# K_line_ESP32.net
KiCad netlist of a schematic drawn in EAGLE
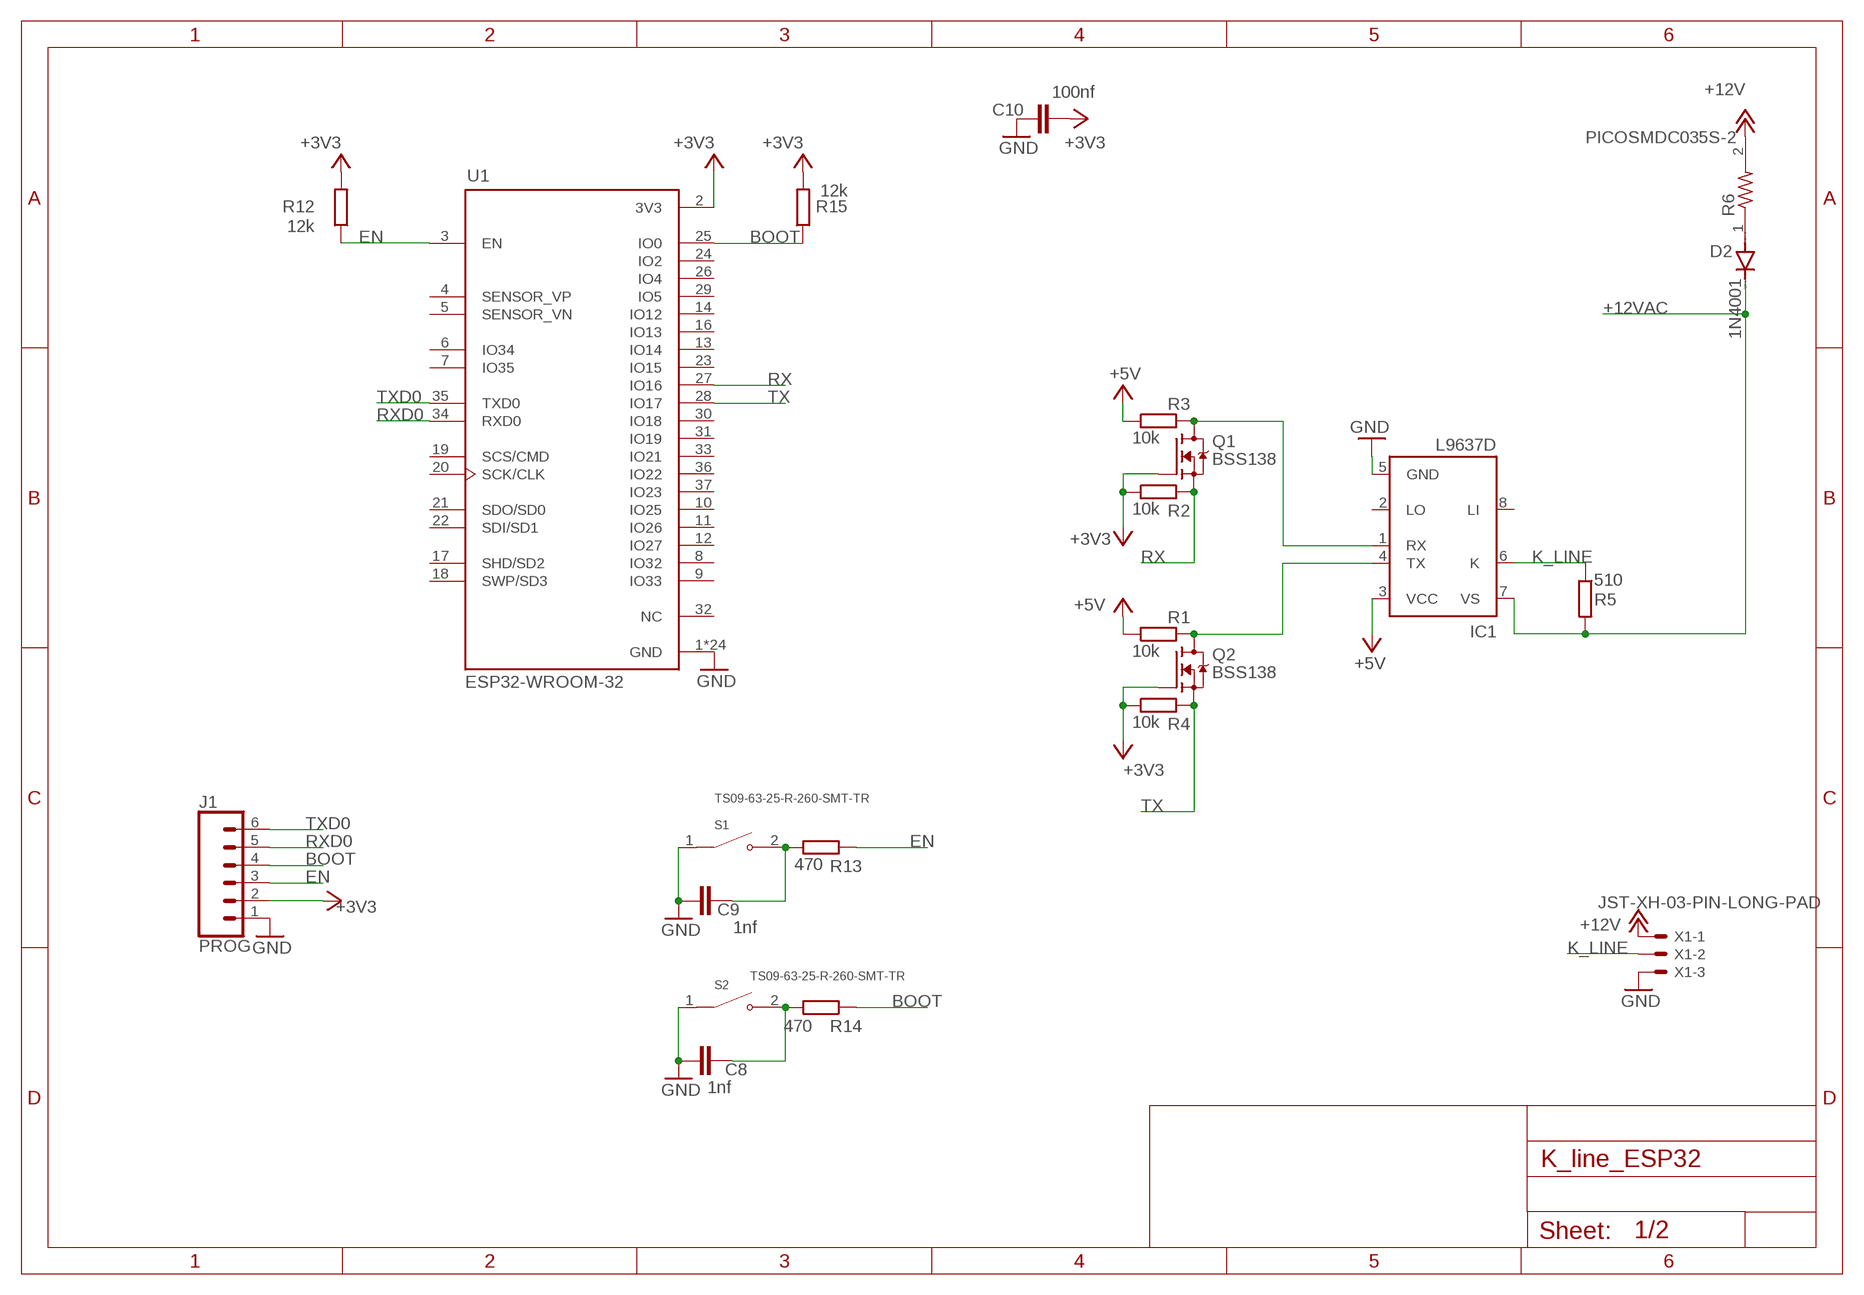
[diagram p0: schematic, sheet 1]
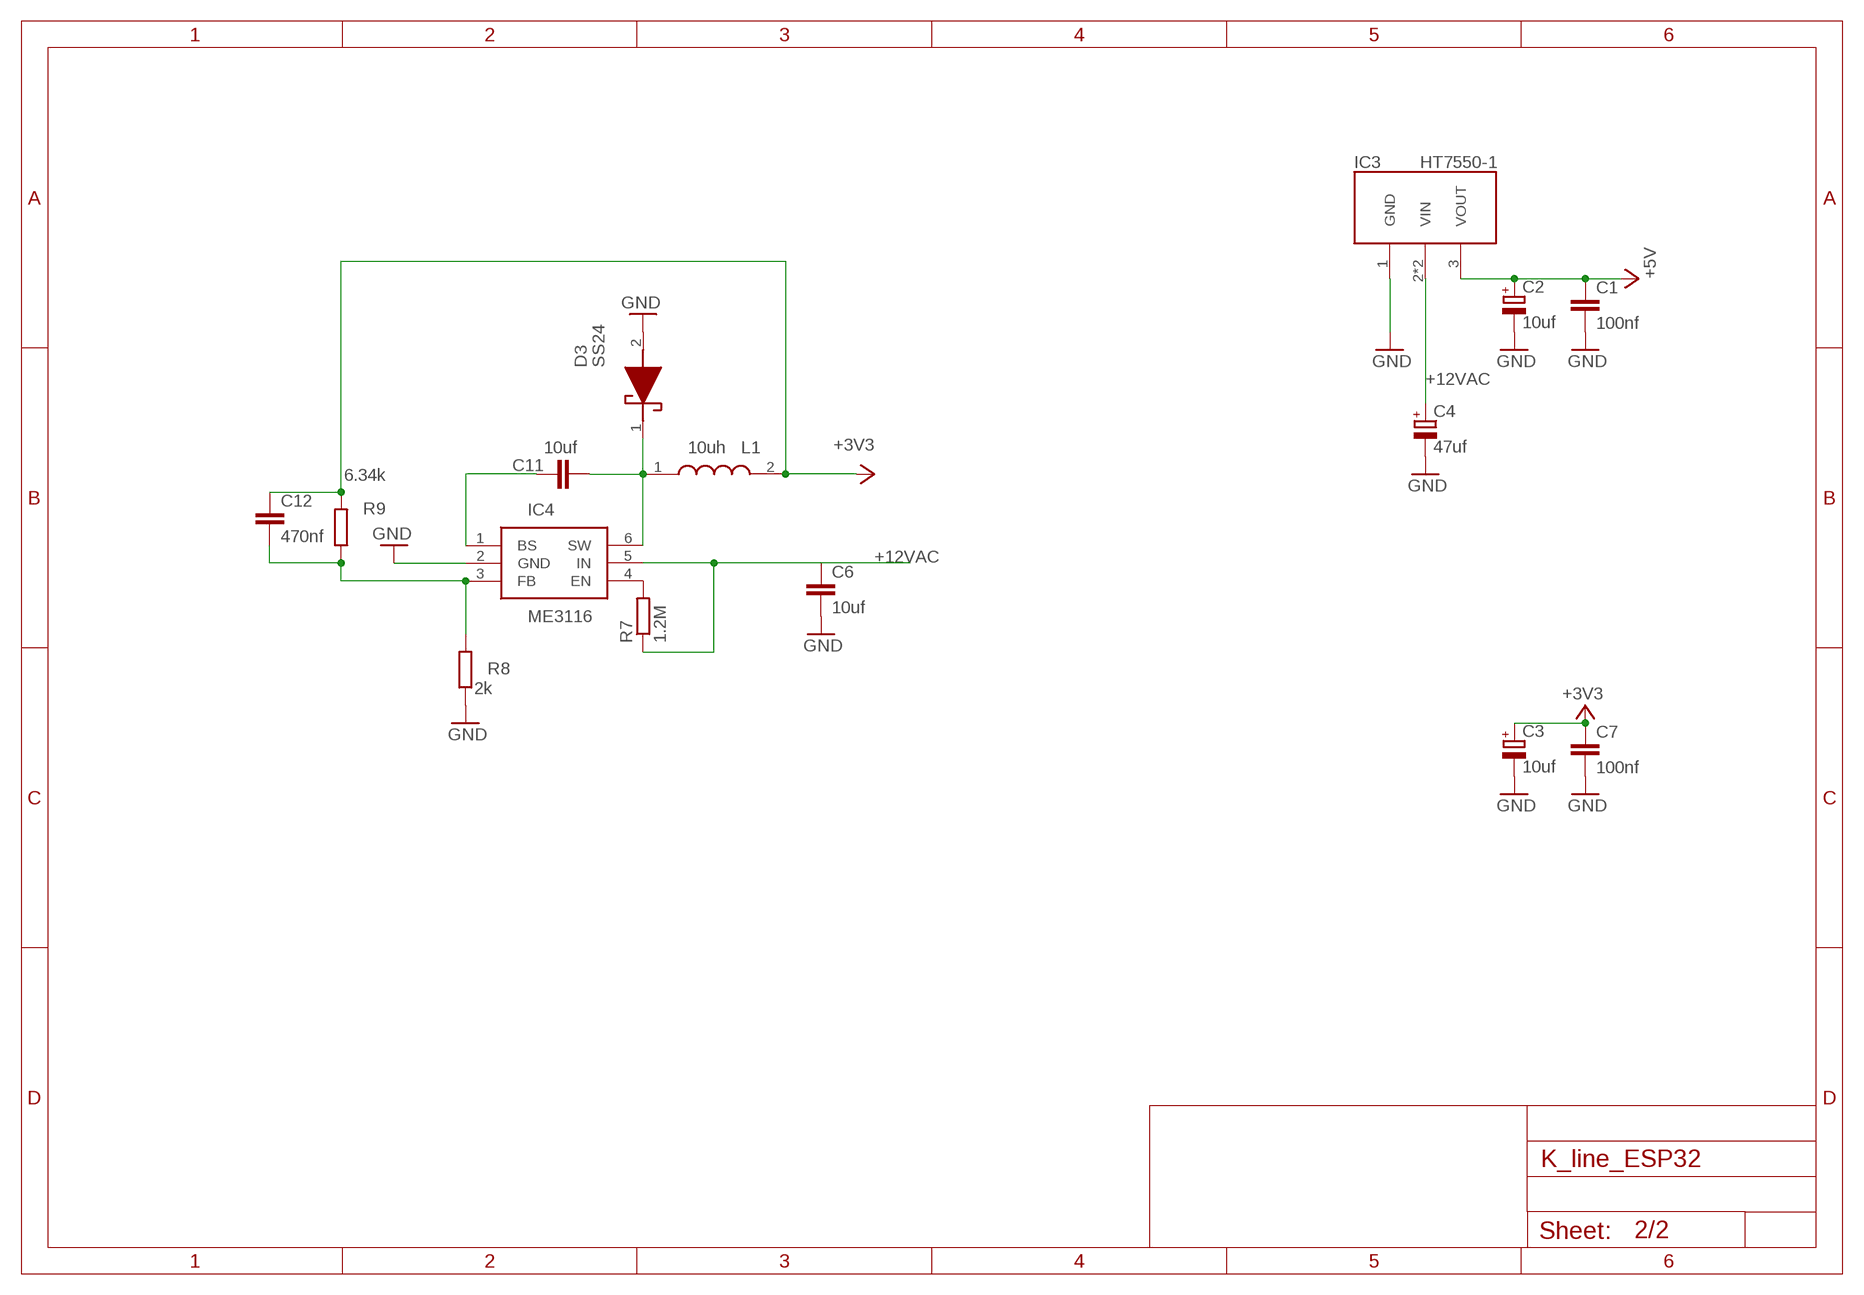
[diagram p1: schematic, sheet 2]

(export (version "E")
  (design (tool "Eeschema 10.0.6"))
  (components
    (comp (ref "C8")
      (value "1nf")
      (footprint "eagle-import:C0805K")
      (libsource (lib "eagle-import") (part "C-EUC0805K"))
    )
    (comp (ref "C9")
      (value "1nf")
      (footprint "eagle-import:C0805K")
      (libsource (lib "eagle-import") (part "C-EUC0805K"))
    )
    (comp (ref "C10")
      (value "100nf")
      (footprint "eagle-import:C0805K")
      (libsource (lib "eagle-import") (part "C-EUC0805K"))
    )
    (comp (ref "D2")
      (value "1N4001")
      (footprint "eagle-import:DO214AA")
      (libsource (lib "eagle-import") (part "DIODE-DO214AA"))
    )
    (comp (ref "IC1")
      (value "L9637D")
      (footprint "eagle-import:SO08")
      (fields (field (name "MF") "STMicroelectronics"))
      (libsource (lib "eagle-import") (part "L9637D"))
    )
    (comp (ref "J1")
      (value "PROG")
      (footprint "eagle-import:1X06")
      (libsource (lib "eagle-import") (part "CONN_06SILK_FEMALE_PTH"))
    )
    (comp (ref "Q1")
      (value "BSS138")
      (footprint "eagle-import:SOT95P240X111-3N")
      (fields (field (name "MF") "Diodes Inc."))
      (libsource (lib "eagle-import") (part "BSS138"))
    )
    (comp (ref "Q2")
      (value "BSS138")
      (footprint "eagle-import:SOT95P240X111-3N")
      (fields (field (name "MF") "Diodes Inc."))
      (libsource (lib "eagle-import") (part "BSS138"))
    )
    (comp (ref "R1")
      (value "10k")
      (footprint "eagle-import:R0805")
      (libsource (lib "eagle-import") (part "R-EU_R0805"))
    )
    (comp (ref "R2")
      (value "10k")
      (footprint "eagle-import:R0805")
      (libsource (lib "eagle-import") (part "R-EU_R0805"))
    )
    (comp (ref "R3")
      (value "10k")
      (footprint "eagle-import:R0805")
      (libsource (lib "eagle-import") (part "R-EU_R0805"))
    )
    (comp (ref "R4")
      (value "10k")
      (footprint "eagle-import:R0805")
      (libsource (lib "eagle-import") (part "R-EU_R0805"))
    )
    (comp (ref "R5")
      (value "510")
      (footprint "eagle-import:R0805")
      (libsource (lib "eagle-import") (part "R-EU_R0805"))
    )
    (comp (ref "R6")
      (value "PICOSMDC035S-2")
      (footprint "eagle-import:RESC2012X65N")
      (fields (field (name "MF") "Littelfuse Inc."))
      (libsource (lib "eagle-import") (part "PICOSMDC035S-2"))
    )
    (comp (ref "R12")
      (value "12k")
      (footprint "eagle-import:R0805")
      (libsource (lib "eagle-import") (part "R-EU_R0805"))
    )
    (comp (ref "R13")
      (value "470")
      (footprint "eagle-import:R0805")
      (libsource (lib "eagle-import") (part "R-EU_R0805"))
    )
    (comp (ref "R14")
      (value "470")
      (footprint "eagle-import:R0805")
      (libsource (lib "eagle-import") (part "R-EU_R0805"))
    )
    (comp (ref "R15")
      (value "12k")
      (footprint "eagle-import:R0805")
      (libsource (lib "eagle-import") (part "R-EU_R0805"))
    )
    (comp (ref "S1")
      (value "TS09-63-25-R-260-SMT-TR")
      (footprint "eagle-import:SW_TS09-63-25-R-260-SMT-TR")
      (fields (field (name "MF") "CUI Devices"))
      (libsource (lib "eagle-import") (part "TS09-63-25-R-260-SMT-TR"))
    )
    (comp (ref "S2")
      (value "TS09-63-25-R-260-SMT-TR")
      (footprint "eagle-import:SW_TS09-63-25-R-260-SMT-TR")
      (fields (field (name "MF") "CUI Devices"))
      (libsource (lib "eagle-import") (part "TS09-63-25-R-260-SMT-TR"))
    )
    (comp (ref "U1")
      (value "ESP32-WROOM-32")
      (footprint "eagle-import:MODULE_ESP32-WROOM-32")
      (fields (field (name "MF") "Espressif Systems"))
      (libsource (lib "eagle-import") (part "ESP32-WROOM-32"))
    )
    (comp (ref "X1")
      (value "JST-XH-03-PIN-LONG-PAD")
      (footprint "eagle-import:JST-XH-03-PACKAGE-LONG-PAD")
      (libsource (lib "eagle-import") (part "JST-XH-03-PIN-LONG-PAD"))
    )
    (comp (ref "C1")
      (value "100nf")
      (footprint "eagle-import:C0805K")
      (libsource (lib "eagle-import") (part "C-EUC0805K"))
    )
    (comp (ref "C2")
      (value "10uf")
      (footprint "eagle-import:CT3216")
      (libsource (lib "eagle-import") (part "CPOL-EUCT3216"))
    )
    (comp (ref "C3")
      (value "10uf")
      (footprint "eagle-import:CT3216")
      (libsource (lib "eagle-import") (part "CPOL-EUCT3216"))
    )
    (comp (ref "C4")
      (value "47uf")
      (footprint "eagle-import:CAPMP3528X210N")
      (libsource (lib "eagle-import") (part "C-POLTANTALUM-1411(3528-METRIC)_"))
    )
    (comp (ref "C6")
      (value "10uf")
      (footprint "eagle-import:C0805K")
      (libsource (lib "eagle-import") (part "C-EUC0805K"))
    )
    (comp (ref "C7")
      (value "100nf")
      (footprint "eagle-import:C0805K")
      (libsource (lib "eagle-import") (part "C-EUC0805K"))
    )
    (comp (ref "C11")
      (value "10uf")
      (footprint "eagle-import:C0805K")
      (libsource (lib "eagle-import") (part "C-EUC0805K"))
    )
    (comp (ref "C12")
      (value "470nf")
      (footprint "eagle-import:C0805K")
      (libsource (lib "eagle-import") (part "C-EUC0805K"))
    )
    (comp (ref "D3")
      (value "SS24")
      (footprint "eagle-import:DIOM5436X247N")
      (fields (field (name "MOUSER_PART_NUMBER") "821-SS24"))
      (libsource (lib "eagle-import") (part "SS24"))
    )
    (comp (ref "IC3")
      (value "HT7550-1")
      (footprint "eagle-import:SOT89")
      (fields (field (name "MF") "Holtek"))
      (libsource (lib "eagle-import") (part "HT7550-1"))
    )
    (comp (ref "IC4")
      (value "ME3116")
      (footprint "eagle-import:SOT95P270X145-6N")
      (libsource (lib "eagle-import") (part "ME3116"))
    )
    (comp (ref "L1")
      (value "10uh")
      (footprint "eagle-import:INDPM7366X300N")
      (fields (field (name "MANUFACTURER_PART_NUMBER") "MHCI06030-220M-R8"))
      (libsource (lib "eagle-import") (part "MHCI06030-220M-R8"))
    )
    (comp (ref "R7")
      (value "1.2M")
      (footprint "eagle-import:R0805")
      (libsource (lib "eagle-import") (part "resistor_348_R-EU_R0805"))
    )
    (comp (ref "R8")
      (value "2k")
      (footprint "eagle-import:R0805")
      (libsource (lib "eagle-import") (part "resistor_348_R-EU_R0805"))
    )
    (comp (ref "R9")
      (value "6.34k")
      (footprint "eagle-import:R0805")
      (libsource (lib "eagle-import") (part "resistor_348_R-EU_R0805"))
    )
  )
  (nets
    (net (code "1") (name "+3V3") (class "Default")
      (node (ref "C10") (pin "2") (pinfunction "2_2") (pintype "passive"))
      (node (ref "C12") (pin "1") (pinfunction "1_1") (pintype "passive"))
      (node (ref "C3") (pin "+") (pinfunction "+_+") (pintype "passive"))
      (node (ref "C7") (pin "1") (pinfunction "1_1") (pintype "passive"))
      (node (ref "J1") (pin "2") (pinfunction "2_2") (pintype "passive"))
      (node (ref "L1") (pin "2") (pinfunction "2_2") (pintype "bidirectional"))
      (node (ref "Q1") (pin "1") (pinfunction "G_1") (pintype "passive"))
      (node (ref "Q2") (pin "1") (pinfunction "G_1") (pintype "passive"))
      (node (ref "R12") (pin "2") (pinfunction "2_2") (pintype "passive"))
      (node (ref "R15") (pin "2") (pinfunction "2_2") (pintype "passive"))
      (node (ref "R2") (pin "1") (pinfunction "1_1") (pintype "passive"))
      (node (ref "R4") (pin "1") (pinfunction "1_1") (pintype "passive"))
      (node (ref "R9") (pin "2") (pinfunction "2_2") (pintype "passive"))
      (node (ref "U1") (pin "2") (pinfunction "3V3_2") (pintype "power_in"))
    )
    (net (code "2") (name "+5V") (class "Default")
      (node (ref "C1") (pin "1") (pinfunction "1_1") (pintype "passive"))
      (node (ref "C2") (pin "+") (pinfunction "+_+") (pintype "passive"))
      (node (ref "IC1") (pin "3") (pinfunction "VCC_3") (pintype "power_in"))
      (node (ref "IC3") (pin "3") (pinfunction "VOUT_3") (pintype "bidirectional"))
      (node (ref "R1") (pin "1") (pinfunction "1_1") (pintype "passive"))
      (node (ref "R3") (pin "1") (pinfunction "1_1") (pintype "passive"))
    )
    (net (code "3") (name "+12V") (class "Default")
      (node (ref "R6") (pin "2") (pinfunction "2_2") (pintype "passive"))
      (node (ref "X1") (pin "1") (pinfunction "S_1") (pintype "passive"))
    )
    (net (code "4") (name "+12VAC") (class "Default")
      (node (ref "C4") (pin "1") (pinfunction "+_1") (pintype "passive"))
      (node (ref "C6") (pin "1") (pinfunction "1_1") (pintype "passive"))
      (node (ref "D2") (pin "C") (pinfunction "C_C") (pintype "passive"))
      (node (ref "IC1") (pin "7") (pinfunction "VS_7") (pintype "power_in"))
      (node (ref "IC3") (pin "2") (pinfunction "VIN_2") (pintype "bidirectional"))
      (node (ref "IC3") (pin "2@1") (pinfunction "VIN_2@1") (pintype "bidirectional"))
      (node (ref "IC4") (pin "5") (pinfunction "IN_5") (pintype "bidirectional"))
      (node (ref "R5") (pin "2") (pinfunction "2_2") (pintype "passive"))
      (node (ref "R7") (pin "1") (pinfunction "1_1") (pintype "passive"))
    )
    (net (code "5") (name "BOOT") (class "Default")
      (node (ref "J1") (pin "4") (pinfunction "4_4") (pintype "passive"))
      (node (ref "R14") (pin "1") (pinfunction "1_1") (pintype "passive"))
      (node (ref "R15") (pin "1") (pinfunction "1_1") (pintype "passive"))
      (node (ref "U1") (pin "25") (pinfunction "IO0_25") (pintype "bidirectional"))
    )
    (net (code "6") (name "EN") (class "Default")
      (node (ref "J1") (pin "3") (pinfunction "3_3") (pintype "passive"))
      (node (ref "R12") (pin "1") (pinfunction "1_1") (pintype "passive"))
      (node (ref "R13") (pin "1") (pinfunction "1_1") (pintype "passive"))
      (node (ref "U1") (pin "3") (pinfunction "EN_3") (pintype "input"))
    )
    (net (code "7") (name "GND") (class "Default")
      (node (ref "C1") (pin "2") (pinfunction "2_2") (pintype "passive"))
      (node (ref "C10") (pin "1") (pinfunction "1_1") (pintype "passive"))
      (node (ref "C2") (pin "-") (pinfunction "-_-") (pintype "passive"))
      (node (ref "C3") (pin "-") (pinfunction "-_-") (pintype "passive"))
      (node (ref "C4") (pin "2") (pinfunction "-_2") (pintype "passive"))
      (node (ref "C6") (pin "2") (pinfunction "2_2") (pintype "passive"))
      (node (ref "C7") (pin "2") (pinfunction "2_2") (pintype "passive"))
      (node (ref "C8") (pin "2") (pinfunction "2_2") (pintype "passive"))
      (node (ref "C9") (pin "1") (pinfunction "1_1") (pintype "passive"))
      (node (ref "D3") (pin "2") (pinfunction "A_2") (pintype "bidirectional"))
      (node (ref "IC1") (pin "5") (pinfunction "GND_5") (pintype "power_in"))
      (node (ref "IC3") (pin "1") (pinfunction "GND_1") (pintype "bidirectional"))
      (node (ref "IC4") (pin "2") (pinfunction "GND_2") (pintype "bidirectional"))
      (node (ref "J1") (pin "1") (pinfunction "1_1") (pintype "passive"))
      (node (ref "R8") (pin "1") (pinfunction "1_1") (pintype "passive"))
      (node (ref "S1") (pin "1") (pinfunction "1_1") (pintype "passive"))
      (node (ref "S2") (pin "1") (pinfunction "1_1") (pintype "passive"))
      (node (ref "U1") (pin "1") (pinfunction "GND_1") (pintype "power_in"))
      (node (ref "U1") (pin "15") (pinfunction "GND_15") (pintype "power_in"))
      (node (ref "U1") (pin "38") (pinfunction "GND_38") (pintype "power_in"))
      (node (ref "U1") (pin "39_1") (pinfunction "GND_39_1") (pintype "power_in"))
      (node (ref "U1") (pin "39_10") (pinfunction "GND_39_10") (pintype "power_in"))
      (node (ref "U1") (pin "39_11") (pinfunction "GND_39_11") (pintype "power_in"))
      (node (ref "U1") (pin "39_12") (pinfunction "GND_39_12") (pintype "power_in"))
      (node (ref "U1") (pin "39_13") (pinfunction "GND_39_13") (pintype "power_in"))
      (node (ref "U1") (pin "39_14") (pinfunction "GND_39_14") (pintype "power_in"))
      (node (ref "U1") (pin "39_15") (pinfunction "GND_39_15") (pintype "power_in"))
      (node (ref "U1") (pin "39_16") (pinfunction "GND_39_16") (pintype "power_in"))
      (node (ref "U1") (pin "39_17") (pinfunction "GND_39_17") (pintype "power_in"))
      (node (ref "U1") (pin "39_18") (pinfunction "GND_39_18") (pintype "power_in"))
      (node (ref "U1") (pin "39_19") (pinfunction "GND_39_19") (pintype "power_in"))
      (node (ref "U1") (pin "39_2") (pinfunction "GND_39_2") (pintype "power_in"))
      (node (ref "U1") (pin "39_20") (pinfunction "GND_39_20") (pintype "power_in"))
      (node (ref "U1") (pin "39_21") (pinfunction "GND_39_21") (pintype "power_in"))
      (node (ref "U1") (pin "39_3") (pinfunction "GND_39_3") (pintype "power_in"))
      (node (ref "U1") (pin "39_4") (pinfunction "GND_39_4") (pintype "power_in"))
      (node (ref "U1") (pin "39_5") (pinfunction "GND_39_5") (pintype "power_in"))
      (node (ref "U1") (pin "39_6") (pinfunction "GND_39_6") (pintype "power_in"))
      (node (ref "U1") (pin "39_7") (pinfunction "GND_39_7") (pintype "power_in"))
      (node (ref "U1") (pin "39_8") (pinfunction "GND_39_8") (pintype "power_in"))
      (node (ref "U1") (pin "39_9") (pinfunction "GND_39_9") (pintype "power_in"))
      (node (ref "X1") (pin "3") (pinfunction "S_3") (pintype "passive"))
    )
    (net (code "8") (name "K_LINE") (class "Default")
      (node (ref "IC1") (pin "6") (pinfunction "K_6") (pintype "input"))
      (node (ref "R5") (pin "1") (pinfunction "1_1") (pintype "passive"))
      (node (ref "X1") (pin "2") (pinfunction "S_2") (pintype "passive"))
    )
    (net (code "9") (name "Net-(C8-Pad1)") (class "Default")
      (node (ref "C8") (pin "1") (pinfunction "1_1") (pintype "passive"))
      (node (ref "R14") (pin "2") (pinfunction "2_2") (pintype "passive"))
      (node (ref "S2") (pin "2") (pinfunction "2_2") (pintype "passive"))
    )
    (net (code "10") (name "Net-(C9-Pad2)") (class "Default")
      (node (ref "C9") (pin "2") (pinfunction "2_2") (pintype "passive"))
      (node (ref "R13") (pin "2") (pinfunction "2_2") (pintype "passive"))
      (node (ref "S1") (pin "2") (pinfunction "2_2") (pintype "passive"))
    )
    (net (code "11") (name "Net-(D2-PadA)") (class "Default")
      (node (ref "D2") (pin "A") (pinfunction "A_A") (pintype "passive"))
      (node (ref "R6") (pin "1") (pinfunction "1_1") (pintype "passive"))
    )
    (net (code "12") (name "Net-(D3-K)") (class "Default")
      (node (ref "C11") (pin "2") (pinfunction "2_2") (pintype "passive"))
      (node (ref "D3") (pin "1") (pinfunction "K_1") (pintype "bidirectional"))
      (node (ref "IC4") (pin "6") (pinfunction "SW_6") (pintype "bidirectional"))
      (node (ref "L1") (pin "1") (pinfunction "1_1") (pintype "bidirectional"))
    )
    (net (code "13") (name "Net-(IC1-RX)") (class "Default")
      (node (ref "IC1") (pin "1") (pinfunction "RX_1") (pintype "output"))
      (node (ref "Q1") (pin "3") (pinfunction "D_3") (pintype "passive"))
      (node (ref "R3") (pin "2") (pinfunction "2_2") (pintype "passive"))
    )
    (net (code "14") (name "Net-(IC1-TX)") (class "Default")
      (node (ref "IC1") (pin "4") (pinfunction "TX_4") (pintype "input"))
      (node (ref "Q2") (pin "3") (pinfunction "D_3") (pintype "passive"))
      (node (ref "R1") (pin "2") (pinfunction "2_2") (pintype "passive"))
    )
    (net (code "15") (name "Net-(IC4-BS)") (class "Default")
      (node (ref "C11") (pin "1") (pinfunction "1_1") (pintype "passive"))
      (node (ref "IC4") (pin "1") (pinfunction "BS_1") (pintype "bidirectional"))
    )
    (net (code "16") (name "Net-(IC4-EN)") (class "Default")
      (node (ref "IC4") (pin "4") (pinfunction "EN_4") (pintype "bidirectional"))
      (node (ref "R7") (pin "2") (pinfunction "2_2") (pintype "passive"))
    )
    (net (code "17") (name "Net-(IC4-FB)") (class "Default")
      (node (ref "C12") (pin "2") (pinfunction "2_2") (pintype "passive"))
      (node (ref "IC4") (pin "3") (pinfunction "FB_3") (pintype "bidirectional"))
      (node (ref "R8") (pin "2") (pinfunction "2_2") (pintype "passive"))
      (node (ref "R9") (pin "1") (pinfunction "1_1") (pintype "passive"))
    )
    (net (code "18") (name "RX") (class "Default")
      (node (ref "Q1") (pin "2") (pinfunction "S_2") (pintype "passive"))
      (node (ref "R2") (pin "2") (pinfunction "2_2") (pintype "passive"))
      (node (ref "U1") (pin "27") (pinfunction "IO16_27") (pintype "bidirectional"))
    )
    (net (code "19") (name "RXD0") (class "Default")
      (node (ref "J1") (pin "5") (pinfunction "5_5") (pintype "passive"))
      (node (ref "U1") (pin "34") (pinfunction "RXD0_34") (pintype "bidirectional"))
    )
    (net (code "20") (name "TX") (class "Default")
      (node (ref "Q2") (pin "2") (pinfunction "S_2") (pintype "passive"))
      (node (ref "R4") (pin "2") (pinfunction "2_2") (pintype "passive"))
      (node (ref "U1") (pin "28") (pinfunction "IO17_28") (pintype "bidirectional"))
    )
    (net (code "21") (name "TXD0") (class "Default")
      (node (ref "J1") (pin "6") (pinfunction "6_6") (pintype "passive"))
      (node (ref "U1") (pin "35") (pinfunction "TXD0_35") (pintype "bidirectional"))
    )
    (net (code "22") (name "unconnected-(IC1-LI-Pad8)") (class "Default")
      (node (ref "IC1") (pin "8") (pinfunction "LI_8") (pintype "input"))
    )
    (net (code "23") (name "unconnected-(IC1-LO-Pad2)") (class "Default")
      (node (ref "IC1") (pin "2") (pinfunction "LO_2") (pintype "output"))
    )
    (net (code "24") (name "unconnected-(U1-IO2-Pad24)") (class "Default")
      (node (ref "U1") (pin "24") (pinfunction "IO2_24") (pintype "bidirectional"))
    )
    (net (code "25") (name "unconnected-(U1-IO4-Pad26)") (class "Default")
      (node (ref "U1") (pin "26") (pinfunction "IO4_26") (pintype "bidirectional"))
    )
    (net (code "26") (name "unconnected-(U1-IO5-Pad29)") (class "Default")
      (node (ref "U1") (pin "29") (pinfunction "IO5_29") (pintype "bidirectional"))
    )
    (net (code "27") (name "unconnected-(U1-IO12-Pad14)") (class "Default")
      (node (ref "U1") (pin "14") (pinfunction "IO12_14") (pintype "bidirectional"))
    )
    (net (code "28") (name "unconnected-(U1-IO13-Pad16)") (class "Default")
      (node (ref "U1") (pin "16") (pinfunction "IO13_16") (pintype "bidirectional"))
    )
    (net (code "29") (name "unconnected-(U1-IO14-Pad13)") (class "Default")
      (node (ref "U1") (pin "13") (pinfunction "IO14_13") (pintype "bidirectional"))
    )
    (net (code "30") (name "unconnected-(U1-IO15-Pad23)") (class "Default")
      (node (ref "U1") (pin "23") (pinfunction "IO15_23") (pintype "bidirectional"))
    )
    (net (code "31") (name "unconnected-(U1-IO18-Pad30)") (class "Default")
      (node (ref "U1") (pin "30") (pinfunction "IO18_30") (pintype "bidirectional"))
    )
    (net (code "32") (name "unconnected-(U1-IO19-Pad31)") (class "Default")
      (node (ref "U1") (pin "31") (pinfunction "IO19_31") (pintype "bidirectional"))
    )
    (net (code "33") (name "unconnected-(U1-IO21-Pad33)") (class "Default")
      (node (ref "U1") (pin "33") (pinfunction "IO21_33") (pintype "bidirectional"))
    )
    (net (code "34") (name "unconnected-(U1-IO22-Pad36)") (class "Default")
      (node (ref "U1") (pin "36") (pinfunction "IO22_36") (pintype "bidirectional"))
    )
    (net (code "35") (name "unconnected-(U1-IO23-Pad37)") (class "Default")
      (node (ref "U1") (pin "37") (pinfunction "IO23_37") (pintype "bidirectional"))
    )
    (net (code "36") (name "unconnected-(U1-IO25-Pad10)") (class "Default")
      (node (ref "U1") (pin "10") (pinfunction "IO25_10") (pintype "bidirectional"))
    )
    (net (code "37") (name "unconnected-(U1-IO26-Pad11)") (class "Default")
      (node (ref "U1") (pin "11") (pinfunction "IO26_11") (pintype "bidirectional"))
    )
    (net (code "38") (name "unconnected-(U1-IO27-Pad12)") (class "Default")
      (node (ref "U1") (pin "12") (pinfunction "IO27_12") (pintype "bidirectional"))
    )
    (net (code "39") (name "unconnected-(U1-IO32-Pad8)") (class "Default")
      (node (ref "U1") (pin "8") (pinfunction "IO32_8") (pintype "bidirectional"))
    )
    (net (code "40") (name "unconnected-(U1-IO33-Pad9)") (class "Default")
      (node (ref "U1") (pin "9") (pinfunction "IO33_9") (pintype "bidirectional"))
    )
    (net (code "41") (name "unconnected-(U1-IO34-Pad6)") (class "Default")
      (node (ref "U1") (pin "6") (pinfunction "IO34_6") (pintype "input"))
    )
    (net (code "42") (name "unconnected-(U1-IO35-Pad7)") (class "Default")
      (node (ref "U1") (pin "7") (pinfunction "IO35_7") (pintype "input"))
    )
    (net (code "43") (name "unconnected-(U1-NC-Pad32)") (class "Default")
      (node (ref "U1") (pin "32") (pinfunction "NC_32") (pintype "no_connect"))
    )
    (net (code "44") (name "unconnected-(U1-SCK{slash}CLK-Pad20)") (class "Default")
      (node (ref "U1") (pin "20") (pinfunction "SCK/CLK_20") (pintype "bidirectional"))
    )
    (net (code "45") (name "unconnected-(U1-SCS{slash}CMD-Pad19)") (class "Default")
      (node (ref "U1") (pin "19") (pinfunction "SCS/CMD_19") (pintype "bidirectional"))
    )
    (net (code "46") (name "unconnected-(U1-SDI{slash}SD1-Pad22)") (class "Default")
      (node (ref "U1") (pin "22") (pinfunction "SDI/SD1_22") (pintype "bidirectional"))
    )
    (net (code "47") (name "unconnected-(U1-SDO{slash}SD0-Pad21)") (class "Default")
      (node (ref "U1") (pin "21") (pinfunction "SDO/SD0_21") (pintype "bidirectional"))
    )
    (net (code "48") (name "unconnected-(U1-SENSOR_VN-Pad5)") (class "Default")
      (node (ref "U1") (pin "5") (pinfunction "SENSOR_VN_5") (pintype "input"))
    )
    (net (code "49") (name "unconnected-(U1-SENSOR_VP-Pad4)") (class "Default")
      (node (ref "U1") (pin "4") (pinfunction "SENSOR_VP_4") (pintype "input"))
    )
    (net (code "50") (name "unconnected-(U1-SHD{slash}SD2-Pad17)") (class "Default")
      (node (ref "U1") (pin "17") (pinfunction "SHD/SD2_17") (pintype "bidirectional"))
    )
    (net (code "51") (name "unconnected-(U1-SWP{slash}SD3-Pad18)") (class "Default")
      (node (ref "U1") (pin "18") (pinfunction "SWP/SD3_18") (pintype "bidirectional"))
    )
  )
)
